# PlacaE3.net
KiCad netlist of a schematic drawn in Altium Designer
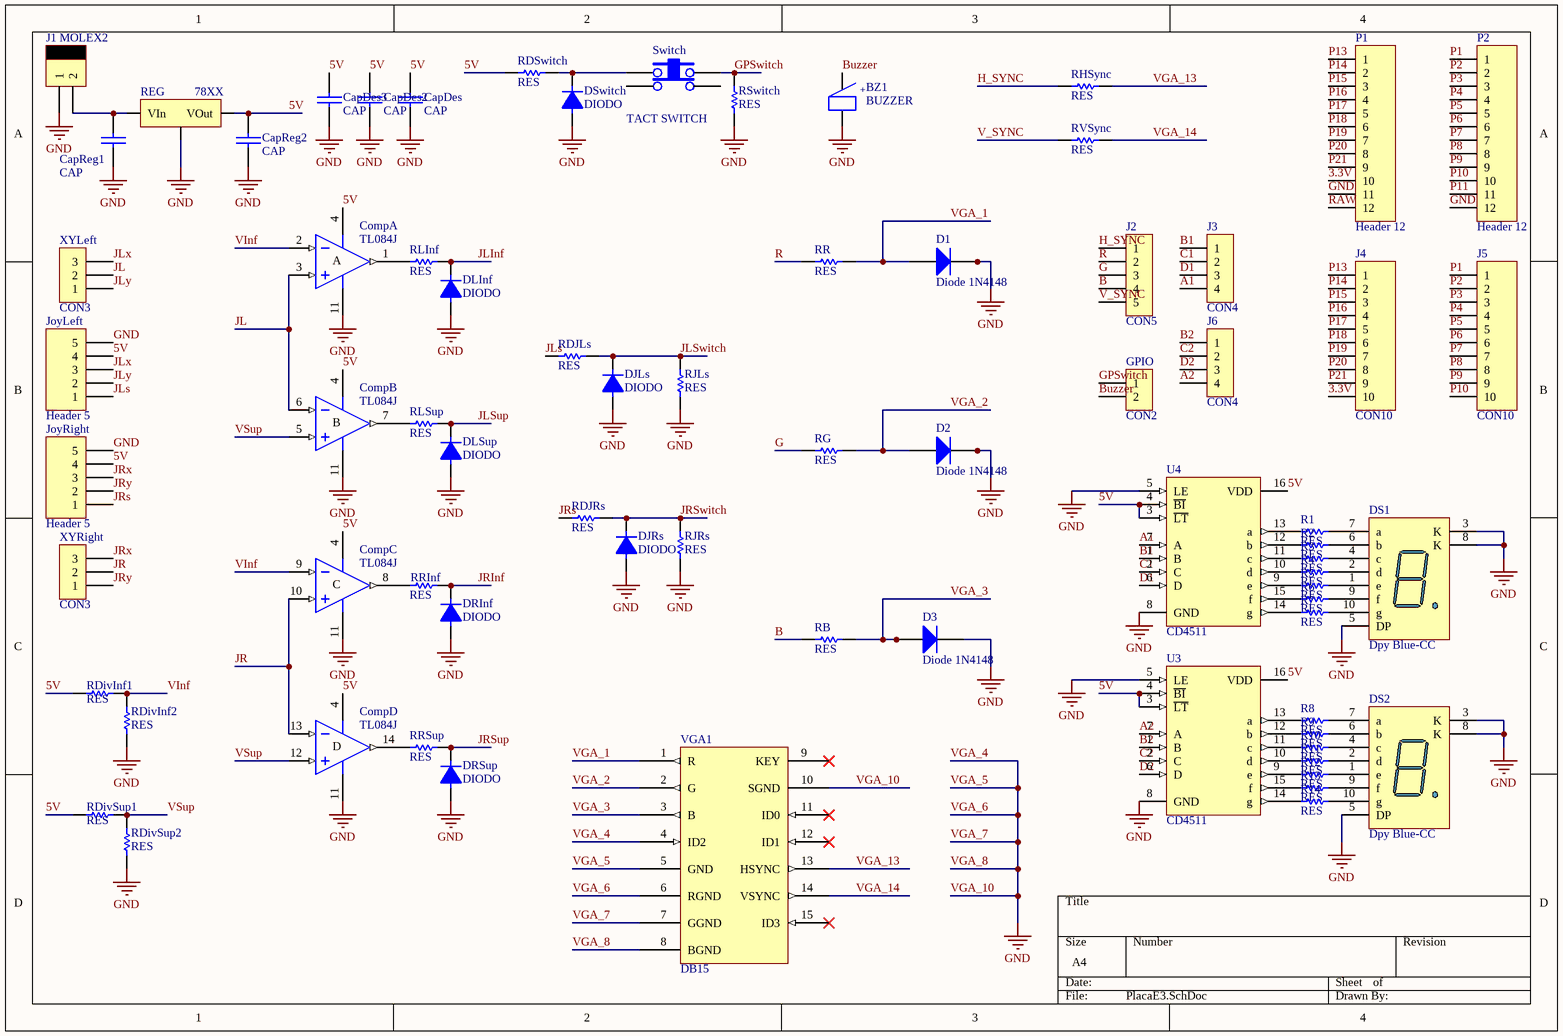
[diagram p0: PlacaE3.SchDoc]

(export (version "E")
  (design (tool "Eeschema 10.0.6"))
  (components
    (comp (ref "BZ1") (value "BUZZER") (footprint "BUZZER 12MM") (libsource (lib "LIBEBAL") (part "BUZZER")))
    (comp (ref "CapDes") (value "CAP") (footprint "CAP200") (libsource (lib "LIBEBAL") (part "CAP")))
    (comp (ref "CapDes2") (value "CAP") (footprint "CAP200") (libsource (lib "LIBEBAL") (part "CAP")))
    (comp (ref "CapDes3") (value "CAP") (footprint "CAP200") (libsource (lib "LIBEBAL") (part "CAP")))
    (comp (ref "CapReg1") (value "CAP") (footprint "CAP200") (libsource (lib "LIBEBAL") (part "CAP")))
    (comp (ref "CapReg2") (value "CAP") (footprint "CAP200") (libsource (lib "LIBEBAL") (part "CAP")))
    (comp (ref "Comp")
      (value "TL084J")
      (footprint "J014")
      (description "JFET-Input Operational Amplifier")
      (fields (field (name "PUBLISHER") "Altium Limited"))
      (libsource (lib "TI Operational Amplifier") (part "TL084J"))
    )
    (comp (ref "D1")
      (value "Diode 1N4148")
      (footprint "DO-35")
      (description "High Conductance Fast Diode")
      (fields (field (name "PUBLISHER") "Altium Limited"))
      (libsource (lib "Miscellaneous Devices") (part "Diode 1N4148"))
    )
    (comp (ref "D2")
      (value "Diode 1N4148")
      (footprint "DO-35")
      (description "High Conductance Fast Diode")
      (fields (field (name "PUBLISHER") "Altium Limited"))
      (libsource (lib "Miscellaneous Devices") (part "Diode 1N4148"))
    )
    (comp (ref "D3")
      (value "Diode 1N4148")
      (footprint "DO-35")
      (description "High Conductance Fast Diode")
      (fields (field (name "PUBLISHER") "Altium Limited"))
      (libsource (lib "Miscellaneous Devices") (part "Diode 1N4148"))
    )
    (comp (ref "DJLs") (value "DIODO") (footprint "DO41") (libsource (lib "LIBEBAL") (part "DIODO")))
    (comp (ref "DJRs") (value "DIODO") (footprint "DO41") (libsource (lib "LIBEBAL") (part "DIODO")))
    (comp (ref "DLInf") (value "DIODO") (footprint "DO41") (libsource (lib "LIBEBAL") (part "DIODO")))
    (comp (ref "DLSup") (value "DIODO") (footprint "DO41") (libsource (lib "LIBEBAL") (part "DIODO")))
    (comp (ref "DRInf") (value "DIODO") (footprint "DO41") (libsource (lib "LIBEBAL") (part "DIODO")))
    (comp (ref "DRSup") (value "DIODO") (footprint "DO41") (libsource (lib "LIBEBAL") (part "DIODO")))
    (comp (ref "DS1")
      (value "Dpy Blue-CC")
      (footprint "H")
      (description "14.2 mm General Purpose Blue 7-Segment Display: CC, RH DP, Gray Surface")
      (fields (field (name "PUBLISHER") "Altium Limited"))
      (libsource (lib "Miscellaneous Devices") (part "Dpy Blue-CC"))
    )
    (comp (ref "DS2")
      (value "Dpy Blue-CC")
      (footprint "H")
      (description "14.2 mm General Purpose Blue 7-Segment Display: CC, RH DP, Gray Surface")
      (fields (field (name "PUBLISHER") "Altium Limited"))
      (libsource (lib "Miscellaneous Devices") (part "Dpy Blue-CC"))
    )
    (comp (ref "DSwitch") (value "DIODO") (footprint "DO41") (libsource (lib "LIBEBAL") (part "DIODO")))
    (comp (ref "GPIO") (value "CON2") (footprint "SIP2") (libsource (lib "LIBEBAL") (part "CON2")))
    (comp (ref "J1") (value "MOLEX2") (footprint "MOLEX2") (libsource (lib "LIBEBAL") (part "MOLEX2")))
    (comp (ref "J2") (value "CON5") (footprint "SIP5") (libsource (lib "LIBEBAL") (part "CON5")))
    (comp (ref "J3") (value "CON4") (footprint "SIP4") (libsource (lib "LIBEBAL") (part "CON4")))
    (comp (ref "J4") (value "CON10") (footprint "SIP10") (libsource (lib "LIBEBAL") (part "CON10")))
    (comp (ref "J5") (value "CON10") (footprint "SIP10") (libsource (lib "LIBEBAL") (part "CON10")))
    (comp (ref "J6") (value "CON4") (footprint "SIP4") (libsource (lib "LIBEBAL") (part "CON4")))
    (comp (ref "JoyLeft")
      (value "Header 5")
      (footprint "HDR1X5")
      (description "Header, 5-Pin")
      (fields (field (name "PUBLISHER") "Altium Limited"))
      (libsource (lib "Miscellaneous Connectors") (part "Header 5"))
    )
    (comp (ref "JoyRight")
      (value "Header 5")
      (footprint "HDR1X5")
      (description "Header, 5-Pin")
      (fields (field (name "PUBLISHER") "Altium Limited"))
      (libsource (lib "Miscellaneous Connectors") (part "Header 5"))
    )
    (comp (ref "P1")
      (value "Header 12")
      (footprint "HDR1X12")
      (description "Header, 12-Pin")
      (fields (field (name "PUBLISHER") "Altium Limited"))
      (libsource (lib "Miscellaneous Connectors") (part "Header 12"))
    )
    (comp (ref "P2")
      (value "Header 12")
      (footprint "HDR1X12")
      (description "Header, 12-Pin")
      (fields (field (name "PUBLISHER") "Altium Limited"))
      (libsource (lib "Miscellaneous Connectors") (part "Header 12"))
    )
    (comp (ref "R1") (value "RES") (footprint "0805") (libsource (lib "LIBEBAL") (part "RES")))
    (comp (ref "R2") (value "RES") (footprint "0805") (libsource (lib "LIBEBAL") (part "RES")))
    (comp (ref "R3") (value "RES") (footprint "0805") (libsource (lib "LIBEBAL") (part "RES")))
    (comp (ref "R4") (value "RES") (footprint "0805") (libsource (lib "LIBEBAL") (part "RES")))
    (comp (ref "R5") (value "RES") (footprint "0805") (libsource (lib "LIBEBAL") (part "RES")))
    (comp (ref "R6") (value "RES") (footprint "0805") (libsource (lib "LIBEBAL") (part "RES")))
    (comp (ref "R7") (value "RES") (footprint "0805") (libsource (lib "LIBEBAL") (part "RES")))
    (comp (ref "R8") (value "RES") (footprint "0805") (libsource (lib "LIBEBAL") (part "RES")))
    (comp (ref "R9") (value "RES") (footprint "0805") (libsource (lib "LIBEBAL") (part "RES")))
    (comp (ref "R10") (value "RES") (footprint "0805") (libsource (lib "LIBEBAL") (part "RES")))
    (comp (ref "R11") (value "RES") (footprint "0805") (libsource (lib "LIBEBAL") (part "RES")))
    (comp (ref "R12") (value "RES") (footprint "0805") (libsource (lib "LIBEBAL") (part "RES")))
    (comp (ref "R13") (value "RES") (footprint "0805") (libsource (lib "LIBEBAL") (part "RES")))
    (comp (ref "R14") (value "RES") (footprint "0805") (libsource (lib "LIBEBAL") (part "RES")))
    (comp (ref "RB") (value "RES") (footprint "RES400") (libsource (lib "LIBEBAL") (part "RES")))
    (comp (ref "RDivInf1") (value "RES") (footprint "RES400") (libsource (lib "LIBEBAL") (part "RES")))
    (comp (ref "RDivInf2") (value "RES") (footprint "RES400") (libsource (lib "LIBEBAL") (part "RES")))
    (comp (ref "RDivSup1") (value "RES") (footprint "RES400") (libsource (lib "LIBEBAL") (part "RES")))
    (comp (ref "RDivSup2") (value "RES") (footprint "RES400") (libsource (lib "LIBEBAL") (part "RES")))
    (comp (ref "RDJLs") (value "RES") (footprint "RES400") (libsource (lib "LIBEBAL") (part "RES")))
    (comp (ref "RDJRs") (value "RES") (footprint "RES400") (libsource (lib "LIBEBAL") (part "RES")))
    (comp (ref "RDSwitch") (value "RES") (footprint "RES400") (libsource (lib "LIBEBAL") (part "RES")))
    (comp (ref "REG")
      (value "78XX")
      (footprint "TO-220 V")
      (description "REGULDOR POSITIVO")
      (libsource (lib "LIBEBAL") (part "78XX"))
    )
    (comp (ref "RG") (value "RES") (footprint "RES400") (libsource (lib "LIBEBAL") (part "RES")))
    (comp (ref "RHSync") (value "RES") (footprint "RES400") (libsource (lib "LIBEBAL") (part "RES")))
    (comp (ref "RJLs") (value "RES") (footprint "RES400") (libsource (lib "LIBEBAL") (part "RES")))
    (comp (ref "RJRs") (value "RES") (footprint "RES400") (libsource (lib "LIBEBAL") (part "RES")))
    (comp (ref "RLInf") (value "RES") (footprint "RES400") (libsource (lib "LIBEBAL") (part "RES")))
    (comp (ref "RLSup") (value "RES") (footprint "RES400") (libsource (lib "LIBEBAL") (part "RES")))
    (comp (ref "RR") (value "RES") (footprint "RES400") (libsource (lib "LIBEBAL") (part "RES")))
    (comp (ref "RRInf") (value "RES") (footprint "RES400") (libsource (lib "LIBEBAL") (part "RES")))
    (comp (ref "RRSup") (value "RES") (footprint "RES400") (libsource (lib "LIBEBAL") (part "RES")))
    (comp (ref "RSwitch") (value "RES") (footprint "RES400") (libsource (lib "LIBEBAL") (part "RES")))
    (comp (ref "RVSync") (value "RES") (footprint "RES400") (libsource (lib "LIBEBAL") (part "RES")))
    (comp (ref "Switch")
      (value "TACT SWITCH")
      (footprint "TACTSWITCH")
      (libsource (lib "LIBEBAL") (part "TACT SWITCH"))
    )
    (comp (ref "U3")
      (value "CD4511")
      (footprint "DIP16")
      (description "BCD to 7 SEGMENTOS")
      (libsource (lib "LIBEBAL") (part "CD4511"))
    )
    (comp (ref "U4")
      (value "CD4511")
      (footprint "DIP16")
      (description "BCD to 7 SEGMENTOS")
      (libsource (lib "LIBEBAL") (part "CD4511"))
    )
    (comp (ref "VGA1")
      (value "DB15")
      (footprint "DB15_DSUB")
      (description "DB15 VGA Male Connector")
      (libsource (lib "VGA_CON") (part "DB15"))
    )
    (comp (ref "XYLeft") (value "CON3") (footprint "SIP3") (libsource (lib "LIBEBAL") (part "CON3")))
    (comp (ref "XYRight") (value "CON3") (footprint "SIP3") (libsource (lib "LIBEBAL") (part "CON3")))
  )
  (nets
    (net (code "1") (name "/3.3V") (class "Default")
      (node (ref "J4") (pin "10") (pinfunction "10_10") (pintype "passive"))
      (node (ref "P1") (pin "10") (pinfunction "10_10") (pintype "passive"))
    )
    (net (code "2") (name "/5V") (class "Default")
      (node (ref "CapDes") (pin "1") (pinfunction "1_1") (pintype "passive"))
      (node (ref "CapDes2") (pin "1") (pinfunction "1_1") (pintype "passive"))
      (node (ref "CapDes3") (pin "1") (pinfunction "1_1") (pintype "passive"))
      (node (ref "CapReg2") (pin "1") (pinfunction "1_1") (pintype "passive"))
      (node (ref "Comp") (pin "4") (pinfunction "V+_4") (pintype "power_in"))
      (node (ref "JoyLeft") (pin "4") (pinfunction "4_4") (pintype "passive"))
      (node (ref "JoyRight") (pin "4") (pinfunction "4_4") (pintype "passive"))
      (node (ref "RDSwitch") (pin "1") (pinfunction "1_1") (pintype "passive"))
      (node (ref "RDivInf1") (pin "1") (pinfunction "1_1") (pintype "passive"))
      (node (ref "RDivSup1") (pin "1") (pinfunction "1_1") (pintype "passive"))
      (node (ref "REG") (pin "3") (pinfunction "VOut_3") (pintype "passive"))
      (node (ref "U3") (pin "16") (pinfunction "VDD_16") (pintype "power_in"))
      (node (ref "U3") (pin "3") (pinfunction "~{LT}_3") (pintype "input"))
      (node (ref "U3") (pin "4") (pinfunction "~{BI}_4") (pintype "input"))
      (node (ref "U4") (pin "16") (pinfunction "VDD_16") (pintype "power_in"))
      (node (ref "U4") (pin "3") (pinfunction "~{LT}_3") (pintype "input"))
      (node (ref "U4") (pin "4") (pinfunction "~{BI}_4") (pintype "input"))
    )
    (net (code "3") (name "/A1") (class "Default")
      (node (ref "J3") (pin "4") (pinfunction "4_4") (pintype "passive"))
      (node (ref "U4") (pin "7") (pinfunction "A_7") (pintype "input"))
    )
    (net (code "4") (name "/A2") (class "Default")
      (node (ref "J6") (pin "4") (pinfunction "4_4") (pintype "passive"))
      (node (ref "U3") (pin "7") (pinfunction "A_7") (pintype "input"))
    )
    (net (code "5") (name "/B") (class "Default")
      (node (ref "J2") (pin "4") (pinfunction "4_4") (pintype "passive"))
      (node (ref "RB") (pin "1") (pinfunction "1_1") (pintype "passive"))
    )
    (net (code "6") (name "/B1") (class "Default")
      (node (ref "J3") (pin "1") (pinfunction "1_1") (pintype "passive"))
      (node (ref "U4") (pin "1") (pinfunction "B_1") (pintype "input"))
    )
    (net (code "7") (name "/B2") (class "Default")
      (node (ref "J6") (pin "1") (pinfunction "1_1") (pintype "passive"))
      (node (ref "U3") (pin "1") (pinfunction "B_1") (pintype "input"))
    )
    (net (code "8") (name "/Buzzer") (class "Default")
      (node (ref "BZ1") (pin "1") (pinfunction "1_1") (pintype "passive"))
      (node (ref "GPIO") (pin "2") (pinfunction "2_2") (pintype "passive"))
    )
    (net (code "9") (name "/C1") (class "Default")
      (node (ref "J3") (pin "2") (pinfunction "2_2") (pintype "passive"))
      (node (ref "U4") (pin "2") (pinfunction "C_2") (pintype "input"))
    )
    (net (code "10") (name "/C2") (class "Default")
      (node (ref "J6") (pin "2") (pinfunction "2_2") (pintype "passive"))
      (node (ref "U3") (pin "2") (pinfunction "C_2") (pintype "input"))
    )
    (net (code "11") (name "/D1") (class "Default")
      (node (ref "J3") (pin "3") (pinfunction "3_3") (pintype "passive"))
      (node (ref "U4") (pin "6") (pinfunction "D_6") (pintype "input"))
    )
    (net (code "12") (name "/D2") (class "Default")
      (node (ref "J6") (pin "3") (pinfunction "3_3") (pintype "passive"))
      (node (ref "U3") (pin "6") (pinfunction "D_6") (pintype "input"))
    )
    (net (code "13") (name "/G") (class "Default")
      (node (ref "J2") (pin "3") (pinfunction "3_3") (pintype "passive"))
      (node (ref "RG") (pin "1") (pinfunction "1_1") (pintype "passive"))
    )
    (net (code "14") (name "/GPSwitch") (class "Default")
      (node (ref "GPIO") (pin "1") (pinfunction "1_1") (pintype "passive"))
      (node (ref "RSwitch") (pin "2") (pinfunction "2_2") (pintype "passive"))
      (node (ref "Switch") (pin "3") (pinfunction "3_3") (pintype "passive"))
    )
    (net (code "15") (name "/H_SYNC") (class "Default")
      (node (ref "J2") (pin "1") (pinfunction "1_1") (pintype "passive"))
      (node (ref "RHSync") (pin "1") (pinfunction "1_1") (pintype "passive"))
    )
    (net (code "16") (name "/JL") (class "Default")
      (node (ref "Comp") (pin "3") (pinfunction "IN+_3") (pintype "input"))
      (node (ref "Comp") (pin "6") (pinfunction "IN-_6") (pintype "input"))
      (node (ref "XYLeft") (pin "2") (pinfunction "2_2") (pintype "passive"))
    )
    (net (code "17") (name "/JLInf") (class "Default")
      (node (ref "DLInf") (pin "2") (pinfunction "2_2") (pintype "passive"))
      (node (ref "RLInf") (pin "2") (pinfunction "2_2") (pintype "passive"))
    )
    (net (code "18") (name "/JLSup") (class "Default")
      (node (ref "DLSup") (pin "2") (pinfunction "2_2") (pintype "passive"))
      (node (ref "RLSup") (pin "2") (pinfunction "2_2") (pintype "passive"))
    )
    (net (code "19") (name "/JLSwitch") (class "Default")
      (node (ref "DJLs") (pin "2") (pinfunction "2_2") (pintype "passive"))
      (node (ref "RDJLs") (pin "2") (pinfunction "2_2") (pintype "passive"))
      (node (ref "RJLs") (pin "2") (pinfunction "2_2") (pintype "passive"))
    )
    (net (code "20") (name "/JLs") (class "Default")
      (node (ref "JoyLeft") (pin "1") (pinfunction "1_1") (pintype "passive"))
      (node (ref "RDJLs") (pin "1") (pinfunction "1_1") (pintype "passive"))
    )
    (net (code "21") (name "/JLx") (class "Default")
      (node (ref "JoyLeft") (pin "3") (pinfunction "3_3") (pintype "passive"))
      (node (ref "XYLeft") (pin "3") (pinfunction "3_3") (pintype "passive"))
    )
    (net (code "22") (name "/JLy") (class "Default")
      (node (ref "JoyLeft") (pin "2") (pinfunction "2_2") (pintype "passive"))
      (node (ref "XYLeft") (pin "1") (pinfunction "1_1") (pintype "passive"))
    )
    (net (code "23") (name "/JR") (class "Default")
      (node (ref "Comp") (pin "10") (pinfunction "IN+_10") (pintype "input"))
      (node (ref "Comp") (pin "13") (pinfunction "IN-_13") (pintype "input"))
      (node (ref "XYRight") (pin "2") (pinfunction "2_2") (pintype "passive"))
    )
    (net (code "24") (name "/JRInf") (class "Default")
      (node (ref "DRInf") (pin "2") (pinfunction "2_2") (pintype "passive"))
      (node (ref "RRInf") (pin "2") (pinfunction "2_2") (pintype "passive"))
    )
    (net (code "25") (name "/JRSup") (class "Default")
      (node (ref "DRSup") (pin "2") (pinfunction "2_2") (pintype "passive"))
      (node (ref "RRSup") (pin "2") (pinfunction "2_2") (pintype "passive"))
    )
    (net (code "26") (name "/JRSwitch") (class "Default")
      (node (ref "DJRs") (pin "2") (pinfunction "2_2") (pintype "passive"))
      (node (ref "RDJRs") (pin "2") (pinfunction "2_2") (pintype "passive"))
      (node (ref "RJRs") (pin "2") (pinfunction "2_2") (pintype "passive"))
    )
    (net (code "27") (name "/JRs") (class "Default")
      (node (ref "JoyRight") (pin "1") (pinfunction "1_1") (pintype "passive"))
      (node (ref "RDJRs") (pin "1") (pinfunction "1_1") (pintype "passive"))
    )
    (net (code "28") (name "/JRx") (class "Default")
      (node (ref "JoyRight") (pin "3") (pinfunction "3_3") (pintype "passive"))
      (node (ref "XYRight") (pin "3") (pinfunction "3_3") (pintype "passive"))
    )
    (net (code "29") (name "/JRy") (class "Default")
      (node (ref "JoyRight") (pin "2") (pinfunction "2_2") (pintype "passive"))
      (node (ref "XYRight") (pin "1") (pinfunction "1_1") (pintype "passive"))
    )
    (net (code "30") (name "/P1") (class "Default")
      (node (ref "J5") (pin "1") (pinfunction "1_1") (pintype "passive"))
      (node (ref "P2") (pin "1") (pinfunction "1_1") (pintype "passive"))
    )
    (net (code "31") (name "/P2") (class "Default")
      (node (ref "J5") (pin "2") (pinfunction "2_2") (pintype "passive"))
      (node (ref "P2") (pin "2") (pinfunction "2_2") (pintype "passive"))
    )
    (net (code "32") (name "/P3") (class "Default")
      (node (ref "J5") (pin "3") (pinfunction "3_3") (pintype "passive"))
      (node (ref "P2") (pin "3") (pinfunction "3_3") (pintype "passive"))
    )
    (net (code "33") (name "/P4") (class "Default")
      (node (ref "J5") (pin "4") (pinfunction "4_4") (pintype "passive"))
      (node (ref "P2") (pin "4") (pinfunction "4_4") (pintype "passive"))
    )
    (net (code "34") (name "/P5") (class "Default")
      (node (ref "J5") (pin "5") (pinfunction "5_5") (pintype "passive"))
      (node (ref "P2") (pin "5") (pinfunction "5_5") (pintype "passive"))
    )
    (net (code "35") (name "/P6") (class "Default")
      (node (ref "J5") (pin "6") (pinfunction "6_6") (pintype "passive"))
      (node (ref "P2") (pin "6") (pinfunction "6_6") (pintype "passive"))
    )
    (net (code "36") (name "/P7") (class "Default")
      (node (ref "J5") (pin "7") (pinfunction "7_7") (pintype "passive"))
      (node (ref "P2") (pin "7") (pinfunction "7_7") (pintype "passive"))
    )
    (net (code "37") (name "/P8") (class "Default")
      (node (ref "J5") (pin "8") (pinfunction "8_8") (pintype "passive"))
      (node (ref "P2") (pin "8") (pinfunction "8_8") (pintype "passive"))
    )
    (net (code "38") (name "/P9") (class "Default")
      (node (ref "J5") (pin "9") (pinfunction "9_9") (pintype "passive"))
      (node (ref "P2") (pin "9") (pinfunction "9_9") (pintype "passive"))
    )
    (net (code "39") (name "/P10") (class "Default")
      (node (ref "J5") (pin "10") (pinfunction "10_10") (pintype "passive"))
      (node (ref "P2") (pin "10") (pinfunction "10_10") (pintype "passive"))
    )
    (net (code "40") (name "/P11") (class "Default")
      (node (ref "P2") (pin "11") (pinfunction "11_11") (pintype "passive"))
    )
    (net (code "41") (name "/P13") (class "Default")
      (node (ref "J4") (pin "1") (pinfunction "1_1") (pintype "passive"))
      (node (ref "P1") (pin "1") (pinfunction "1_1") (pintype "passive"))
    )
    (net (code "42") (name "/P14") (class "Default")
      (node (ref "J4") (pin "2") (pinfunction "2_2") (pintype "passive"))
      (node (ref "P1") (pin "2") (pinfunction "2_2") (pintype "passive"))
    )
    (net (code "43") (name "/P15") (class "Default")
      (node (ref "J4") (pin "3") (pinfunction "3_3") (pintype "passive"))
      (node (ref "P1") (pin "3") (pinfunction "3_3") (pintype "passive"))
    )
    (net (code "44") (name "/P16") (class "Default")
      (node (ref "J4") (pin "4") (pinfunction "4_4") (pintype "passive"))
      (node (ref "P1") (pin "4") (pinfunction "4_4") (pintype "passive"))
    )
    (net (code "45") (name "/P17") (class "Default")
      (node (ref "J4") (pin "5") (pinfunction "5_5") (pintype "passive"))
      (node (ref "P1") (pin "5") (pinfunction "5_5") (pintype "passive"))
    )
    (net (code "46") (name "/P18") (class "Default")
      (node (ref "J4") (pin "6") (pinfunction "6_6") (pintype "passive"))
      (node (ref "P1") (pin "6") (pinfunction "6_6") (pintype "passive"))
    )
    (net (code "47") (name "/P19") (class "Default")
      (node (ref "J4") (pin "7") (pinfunction "7_7") (pintype "passive"))
      (node (ref "P1") (pin "7") (pinfunction "7_7") (pintype "passive"))
    )
    (net (code "48") (name "/P20") (class "Default")
      (node (ref "J4") (pin "8") (pinfunction "8_8") (pintype "passive"))
      (node (ref "P1") (pin "8") (pinfunction "8_8") (pintype "passive"))
    )
    (net (code "49") (name "/P21") (class "Default")
      (node (ref "J4") (pin "9") (pinfunction "9_9") (pintype "passive"))
      (node (ref "P1") (pin "9") (pinfunction "9_9") (pintype "passive"))
    )
    (net (code "50") (name "/R") (class "Default")
      (node (ref "J2") (pin "2") (pinfunction "2_2") (pintype "passive"))
      (node (ref "RR") (pin "1") (pinfunction "1_1") (pintype "passive"))
    )
    (net (code "51") (name "/RAW") (class "Default")
      (node (ref "P1") (pin "12") (pinfunction "12_12") (pintype "passive"))
    )
    (net (code "52") (name "/VGA_1") (class "Default")
      (node (ref "D1") (pin "1") (pinfunction "A_1") (pintype "passive"))
      (node (ref "RR") (pin "2") (pinfunction "2_2") (pintype "passive"))
      (node (ref "VGA1") (pin "1") (pinfunction "R_1") (pintype "output"))
    )
    (net (code "53") (name "/VGA_2") (class "Default")
      (node (ref "D2") (pin "1") (pinfunction "A_1") (pintype "passive"))
      (node (ref "RG") (pin "2") (pinfunction "2_2") (pintype "passive"))
      (node (ref "VGA1") (pin "2") (pinfunction "G_2") (pintype "output"))
    )
    (net (code "54") (name "/VGA_3") (class "Default")
      (node (ref "D3") (pin "1") (pinfunction "A_1") (pintype "passive"))
      (node (ref "RB") (pin "2") (pinfunction "2_2") (pintype "passive"))
      (node (ref "VGA1") (pin "3") (pinfunction "B_3") (pintype "output"))
    )
    (net (code "55") (name "/VGA_13") (class "Default")
      (node (ref "RHSync") (pin "2") (pinfunction "2_2") (pintype "passive"))
      (node (ref "VGA1") (pin "13") (pinfunction "HSYNC_13") (pintype "output"))
    )
    (net (code "56") (name "/VGA_14") (class "Default")
      (node (ref "RVSync") (pin "2") (pinfunction "2_2") (pintype "passive"))
      (node (ref "VGA1") (pin "14") (pinfunction "VSYNC_14") (pintype "output"))
    )
    (net (code "57") (name "/VInf") (class "Default")
      (node (ref "Comp") (pin "2") (pinfunction "IN-_2") (pintype "input"))
      (node (ref "Comp") (pin "9") (pinfunction "IN-_9") (pintype "input"))
      (node (ref "RDivInf1") (pin "2") (pinfunction "2_2") (pintype "passive"))
      (node (ref "RDivInf2") (pin "2") (pinfunction "2_2") (pintype "passive"))
    )
    (net (code "58") (name "/VSup") (class "Default")
      (node (ref "Comp") (pin "12") (pinfunction "IN+_12") (pintype "input"))
      (node (ref "Comp") (pin "5") (pinfunction "IN+_5") (pintype "input"))
      (node (ref "RDivSup1") (pin "2") (pinfunction "2_2") (pintype "passive"))
      (node (ref "RDivSup2") (pin "2") (pinfunction "2_2") (pintype "passive"))
    )
    (net (code "59") (name "/V_SYNC") (class "Default")
      (node (ref "J2") (pin "5") (pinfunction "5_5") (pintype "passive"))
      (node (ref "RVSync") (pin "1") (pinfunction "1_1") (pintype "passive"))
    )
    (net (code "60") (name "GND") (class "Default")
      (node (ref "BZ1") (pin "2") (pinfunction "2_2") (pintype "passive"))
      (node (ref "CapDes") (pin "2") (pinfunction "2_2") (pintype "passive"))
      (node (ref "CapDes2") (pin "2") (pinfunction "2_2") (pintype "passive"))
      (node (ref "CapDes3") (pin "2") (pinfunction "2_2") (pintype "passive"))
      (node (ref "CapReg1") (pin "2") (pinfunction "2_2") (pintype "passive"))
      (node (ref "CapReg2") (pin "2") (pinfunction "2_2") (pintype "passive"))
      (node (ref "Comp") (pin "11") (pinfunction "V-_11") (pintype "power_in"))
      (node (ref "D1") (pin "2") (pinfunction "K_2") (pintype "passive"))
      (node (ref "D2") (pin "2") (pinfunction "K_2") (pintype "passive"))
      (node (ref "D3") (pin "2") (pinfunction "K_2") (pintype "passive"))
      (node (ref "DJLs") (pin "1") (pinfunction "1_1") (pintype "passive"))
      (node (ref "DJRs") (pin "1") (pinfunction "1_1") (pintype "passive"))
      (node (ref "DLInf") (pin "1") (pinfunction "1_1") (pintype "passive"))
      (node (ref "DLSup") (pin "1") (pinfunction "1_1") (pintype "passive"))
      (node (ref "DRInf") (pin "1") (pinfunction "1_1") (pintype "passive"))
      (node (ref "DRSup") (pin "1") (pinfunction "1_1") (pintype "passive"))
      (node (ref "DS1") (pin "3") (pinfunction "K_3") (pintype "passive"))
      (node (ref "DS1") (pin "5") (pinfunction "DP_5") (pintype "passive"))
      (node (ref "DS1") (pin "8") (pinfunction "K_8") (pintype "passive"))
      (node (ref "DS2") (pin "3") (pinfunction "K_3") (pintype "passive"))
      (node (ref "DS2") (pin "5") (pinfunction "DP_5") (pintype "passive"))
      (node (ref "DS2") (pin "8") (pinfunction "K_8") (pintype "passive"))
      (node (ref "DSwitch") (pin "1") (pinfunction "1_1") (pintype "passive"))
      (node (ref "J1") (pin "1") (pinfunction "1_1") (pintype "passive"))
      (node (ref "JoyLeft") (pin "5") (pinfunction "5_5") (pintype "passive"))
      (node (ref "JoyRight") (pin "5") (pinfunction "5_5") (pintype "passive"))
      (node (ref "P1") (pin "11") (pinfunction "11_11") (pintype "passive"))
      (node (ref "P2") (pin "12") (pinfunction "12_12") (pintype "passive"))
      (node (ref "RDivInf2") (pin "1") (pinfunction "1_1") (pintype "passive"))
      (node (ref "RDivSup2") (pin "1") (pinfunction "1_1") (pintype "passive"))
      (node (ref "REG") (pin "2") (pinfunction "GND_2") (pintype "passive"))
      (node (ref "RJLs") (pin "1") (pinfunction "1_1") (pintype "passive"))
      (node (ref "RJRs") (pin "1") (pinfunction "1_1") (pintype "passive"))
      (node (ref "RSwitch") (pin "1") (pinfunction "1_1") (pintype "passive"))
      (node (ref "U3") (pin "5") (pinfunction "LE_5") (pintype "input"))
      (node (ref "U3") (pin "8") (pinfunction "GND_8") (pintype "power_in"))
      (node (ref "U4") (pin "5") (pinfunction "LE_5") (pintype "input"))
      (node (ref "U4") (pin "8") (pinfunction "GND_8") (pintype "power_in"))
      (node (ref "VGA1") (pin "10") (pinfunction "SGND_10") (pintype "passive"))
      (node (ref "VGA1") (pin "4") (pinfunction "ID2_4") (pintype "input"))
      (node (ref "VGA1") (pin "5") (pinfunction "GND_5") (pintype "passive"))
      (node (ref "VGA1") (pin "6") (pinfunction "RGND_6") (pintype "passive"))
      (node (ref "VGA1") (pin "7") (pinfunction "GGND_7") (pintype "passive"))
      (node (ref "VGA1") (pin "8") (pinfunction "BGND_8") (pintype "passive"))
    )
    (net (code "61") (name "Net-(CompA-OUT)") (class "Default")
      (node (ref "Comp") (pin "1") (pinfunction "OUT_1") (pintype "output"))
      (node (ref "RLInf") (pin "1") (pinfunction "1_1") (pintype "passive"))
    )
    (net (code "62") (name "Net-(CompB-OUT)") (class "Default")
      (node (ref "Comp") (pin "7") (pinfunction "OUT_7") (pintype "output"))
      (node (ref "RLSup") (pin "1") (pinfunction "1_1") (pintype "passive"))
    )
    (net (code "63") (name "Net-(CompC-OUT)") (class "Default")
      (node (ref "Comp") (pin "8") (pinfunction "OUT_8") (pintype "output"))
      (node (ref "RRInf") (pin "1") (pinfunction "1_1") (pintype "passive"))
    )
    (net (code "64") (name "Net-(CompD-OUT)") (class "Default")
      (node (ref "Comp") (pin "14") (pinfunction "OUT_14") (pintype "output"))
      (node (ref "RRSup") (pin "1") (pinfunction "1_1") (pintype "passive"))
    )
    (net (code "65") (name "Net-(DS1-a)") (class "Default")
      (node (ref "DS1") (pin "7") (pinfunction "a_7") (pintype "passive"))
      (node (ref "R1") (pin "2") (pinfunction "2_2") (pintype "passive"))
    )
    (net (code "66") (name "Net-(DS1-b)") (class "Default")
      (node (ref "DS1") (pin "6") (pinfunction "b_6") (pintype "passive"))
      (node (ref "R2") (pin "2") (pinfunction "2_2") (pintype "passive"))
    )
    (net (code "67") (name "Net-(DS1-c)") (class "Default")
      (node (ref "DS1") (pin "4") (pinfunction "c_4") (pintype "passive"))
      (node (ref "R3") (pin "2") (pinfunction "2_2") (pintype "passive"))
    )
    (net (code "68") (name "Net-(DS1-d)") (class "Default")
      (node (ref "DS1") (pin "2") (pinfunction "d_2") (pintype "passive"))
      (node (ref "R4") (pin "2") (pinfunction "2_2") (pintype "passive"))
    )
    (net (code "69") (name "Net-(DS1-e)") (class "Default")
      (node (ref "DS1") (pin "1") (pinfunction "e_1") (pintype "passive"))
      (node (ref "R5") (pin "2") (pinfunction "2_2") (pintype "passive"))
    )
    (net (code "70") (name "Net-(DS1-f)") (class "Default")
      (node (ref "DS1") (pin "9") (pinfunction "f_9") (pintype "passive"))
      (node (ref "R6") (pin "2") (pinfunction "2_2") (pintype "passive"))
    )
    (net (code "71") (name "Net-(DS1-g)") (class "Default")
      (node (ref "DS1") (pin "10") (pinfunction "g_10") (pintype "passive"))
      (node (ref "R7") (pin "2") (pinfunction "2_2") (pintype "passive"))
    )
    (net (code "72") (name "Net-(DS2-a)") (class "Default")
      (node (ref "DS2") (pin "7") (pinfunction "a_7") (pintype "passive"))
      (node (ref "R8") (pin "2") (pinfunction "2_2") (pintype "passive"))
    )
    (net (code "73") (name "Net-(DS2-b)") (class "Default")
      (node (ref "DS2") (pin "6") (pinfunction "b_6") (pintype "passive"))
      (node (ref "R9") (pin "2") (pinfunction "2_2") (pintype "passive"))
    )
    (net (code "74") (name "Net-(DS2-c)") (class "Default")
      (node (ref "DS2") (pin "4") (pinfunction "c_4") (pintype "passive"))
      (node (ref "R10") (pin "2") (pinfunction "2_2") (pintype "passive"))
    )
    (net (code "75") (name "Net-(DS2-d)") (class "Default")
      (node (ref "DS2") (pin "2") (pinfunction "d_2") (pintype "passive"))
      (node (ref "R11") (pin "2") (pinfunction "2_2") (pintype "passive"))
    )
    (net (code "76") (name "Net-(DS2-e)") (class "Default")
      (node (ref "DS2") (pin "1") (pinfunction "e_1") (pintype "passive"))
      (node (ref "R12") (pin "2") (pinfunction "2_2") (pintype "passive"))
    )
    (net (code "77") (name "Net-(DS2-f)") (class "Default")
      (node (ref "DS2") (pin "9") (pinfunction "f_9") (pintype "passive"))
      (node (ref "R13") (pin "2") (pinfunction "2_2") (pintype "passive"))
    )
    (net (code "78") (name "Net-(DS2-g)") (class "Default")
      (node (ref "DS2") (pin "10") (pinfunction "g_10") (pintype "passive"))
      (node (ref "R14") (pin "2") (pinfunction "2_2") (pintype "passive"))
    )
    (net (code "79") (name "Net-(DSwitch-Pad2)") (class "Default")
      (node (ref "DSwitch") (pin "2") (pinfunction "2_2") (pintype "passive"))
      (node (ref "RDSwitch") (pin "2") (pinfunction "2_2") (pintype "passive"))
      (node (ref "Switch") (pin "1") (pinfunction "1_1") (pintype "passive"))
    )
    (net (code "80") (name "Net-(REG-VIn)") (class "Default")
      (node (ref "CapReg1") (pin "1") (pinfunction "1_1") (pintype "passive"))
      (node (ref "J1") (pin "2") (pinfunction "2_2") (pintype "passive"))
      (node (ref "REG") (pin "1") (pinfunction "VIn_1") (pintype "passive"))
    )
    (net (code "81") (name "Net-(U3-a)") (class "Default")
      (node (ref "R8") (pin "1") (pinfunction "1_1") (pintype "passive"))
      (node (ref "U3") (pin "13") (pinfunction "a_13") (pintype "output"))
    )
    (net (code "82") (name "Net-(U3-b)") (class "Default")
      (node (ref "R9") (pin "1") (pinfunction "1_1") (pintype "passive"))
      (node (ref "U3") (pin "12") (pinfunction "b_12") (pintype "output"))
    )
    (net (code "83") (name "Net-(U3-c)") (class "Default")
      (node (ref "R10") (pin "1") (pinfunction "1_1") (pintype "passive"))
      (node (ref "U3") (pin "11") (pinfunction "c_11") (pintype "output"))
    )
    (net (code "84") (name "Net-(U3-d)") (class "Default")
      (node (ref "R11") (pin "1") (pinfunction "1_1") (pintype "passive"))
      (node (ref "U3") (pin "10") (pinfunction "d_10") (pintype "output"))
    )
    (net (code "85") (name "Net-(U3-e)") (class "Default")
      (node (ref "R12") (pin "1") (pinfunction "1_1") (pintype "passive"))
      (node (ref "U3") (pin "9") (pinfunction "e_9") (pintype "output"))
    )
    (net (code "86") (name "Net-(U3-f)") (class "Default")
      (node (ref "R13") (pin "1") (pinfunction "1_1") (pintype "passive"))
      (node (ref "U3") (pin "15") (pinfunction "f_15") (pintype "output"))
    )
    (net (code "87") (name "Net-(U3-g)") (class "Default")
      (node (ref "R14") (pin "1") (pinfunction "1_1") (pintype "passive"))
      (node (ref "U3") (pin "14") (pinfunction "g_14") (pintype "output"))
    )
    (net (code "88") (name "Net-(U4-a)") (class "Default")
      (node (ref "R1") (pin "1") (pinfunction "1_1") (pintype "passive"))
      (node (ref "U4") (pin "13") (pinfunction "a_13") (pintype "output"))
    )
    (net (code "89") (name "Net-(U4-b)") (class "Default")
      (node (ref "R2") (pin "1") (pinfunction "1_1") (pintype "passive"))
      (node (ref "U4") (pin "12") (pinfunction "b_12") (pintype "output"))
    )
    (net (code "90") (name "Net-(U4-c)") (class "Default")
      (node (ref "R3") (pin "1") (pinfunction "1_1") (pintype "passive"))
      (node (ref "U4") (pin "11") (pinfunction "c_11") (pintype "output"))
    )
    (net (code "91") (name "Net-(U4-d)") (class "Default")
      (node (ref "R4") (pin "1") (pinfunction "1_1") (pintype "passive"))
      (node (ref "U4") (pin "10") (pinfunction "d_10") (pintype "output"))
    )
    (net (code "92") (name "Net-(U4-e)") (class "Default")
      (node (ref "R5") (pin "1") (pinfunction "1_1") (pintype "passive"))
      (node (ref "U4") (pin "9") (pinfunction "e_9") (pintype "output"))
    )
    (net (code "93") (name "Net-(U4-f)") (class "Default")
      (node (ref "R6") (pin "1") (pinfunction "1_1") (pintype "passive"))
      (node (ref "U4") (pin "15") (pinfunction "f_15") (pintype "output"))
    )
    (net (code "94") (name "Net-(U4-g)") (class "Default")
      (node (ref "R7") (pin "1") (pinfunction "1_1") (pintype "passive"))
      (node (ref "U4") (pin "14") (pinfunction "g_14") (pintype "output"))
    )
    (net (code "95") (name "unconnected-(Switch-Pad2)") (class "Default")
      (node (ref "Switch") (pin "2") (pinfunction "2_2") (pintype "passive"))
    )
    (net (code "96") (name "unconnected-(Switch-Pad4)") (class "Default")
      (node (ref "Switch") (pin "4") (pinfunction "4_4") (pintype "passive"))
    )
    (net (code "97") (name "unconnected-(VGA1-ID0-Pad11)") (class "Default")
      (node (ref "VGA1") (pin "11") (pinfunction "ID0_11") (pintype "input+no_connect"))
    )
    (net (code "98") (name "unconnected-(VGA1-ID1-Pad12)") (class "Default")
      (node (ref "VGA1") (pin "12") (pinfunction "ID1_12") (pintype "input+no_connect"))
    )
    (net (code "99") (name "unconnected-(VGA1-ID3-Pad15)") (class "Default")
      (node (ref "VGA1") (pin "15") (pinfunction "ID3_15") (pintype "input+no_connect"))
    )
    (net (code "100") (name "unconnected-(VGA1-KEY-Pad9)") (class "Default")
      (node (ref "VGA1") (pin "9") (pinfunction "KEY_9") (pintype "passive+no_connect"))
    )
  )
)
